# New_Schematic.net
KiCad netlist of a schematic drawn in EAGLE
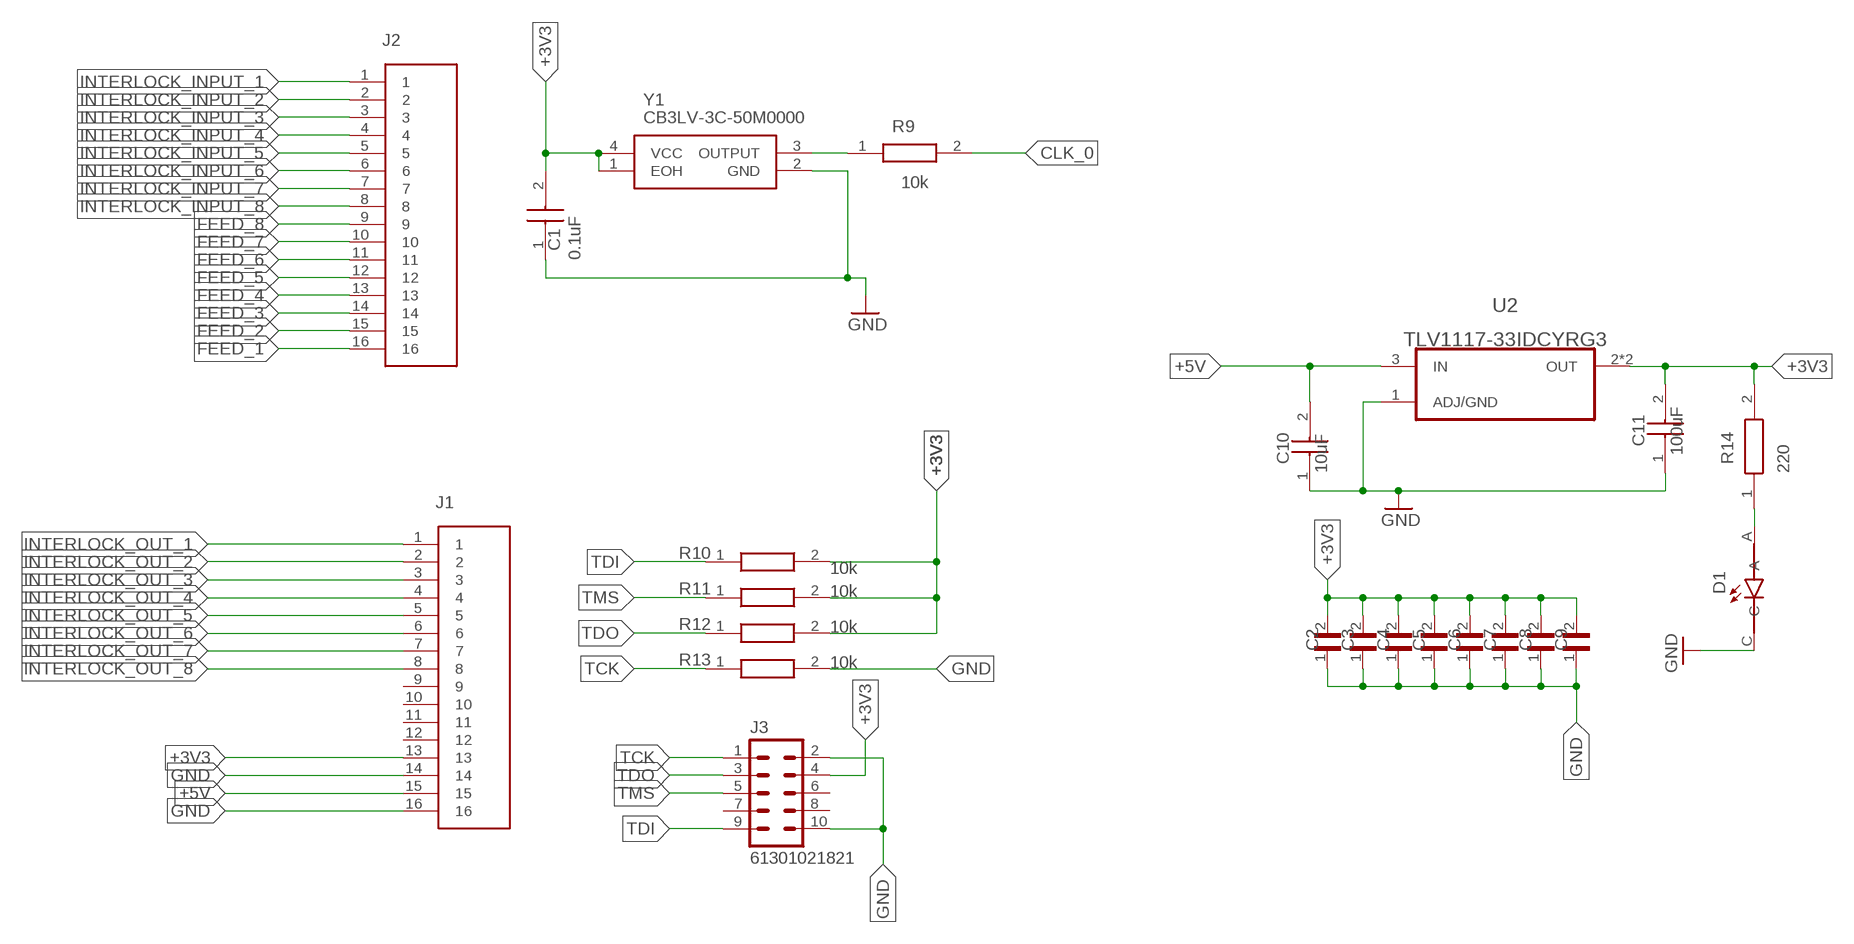
[diagram p0: schematic, sheet 1, part 1 of 2]
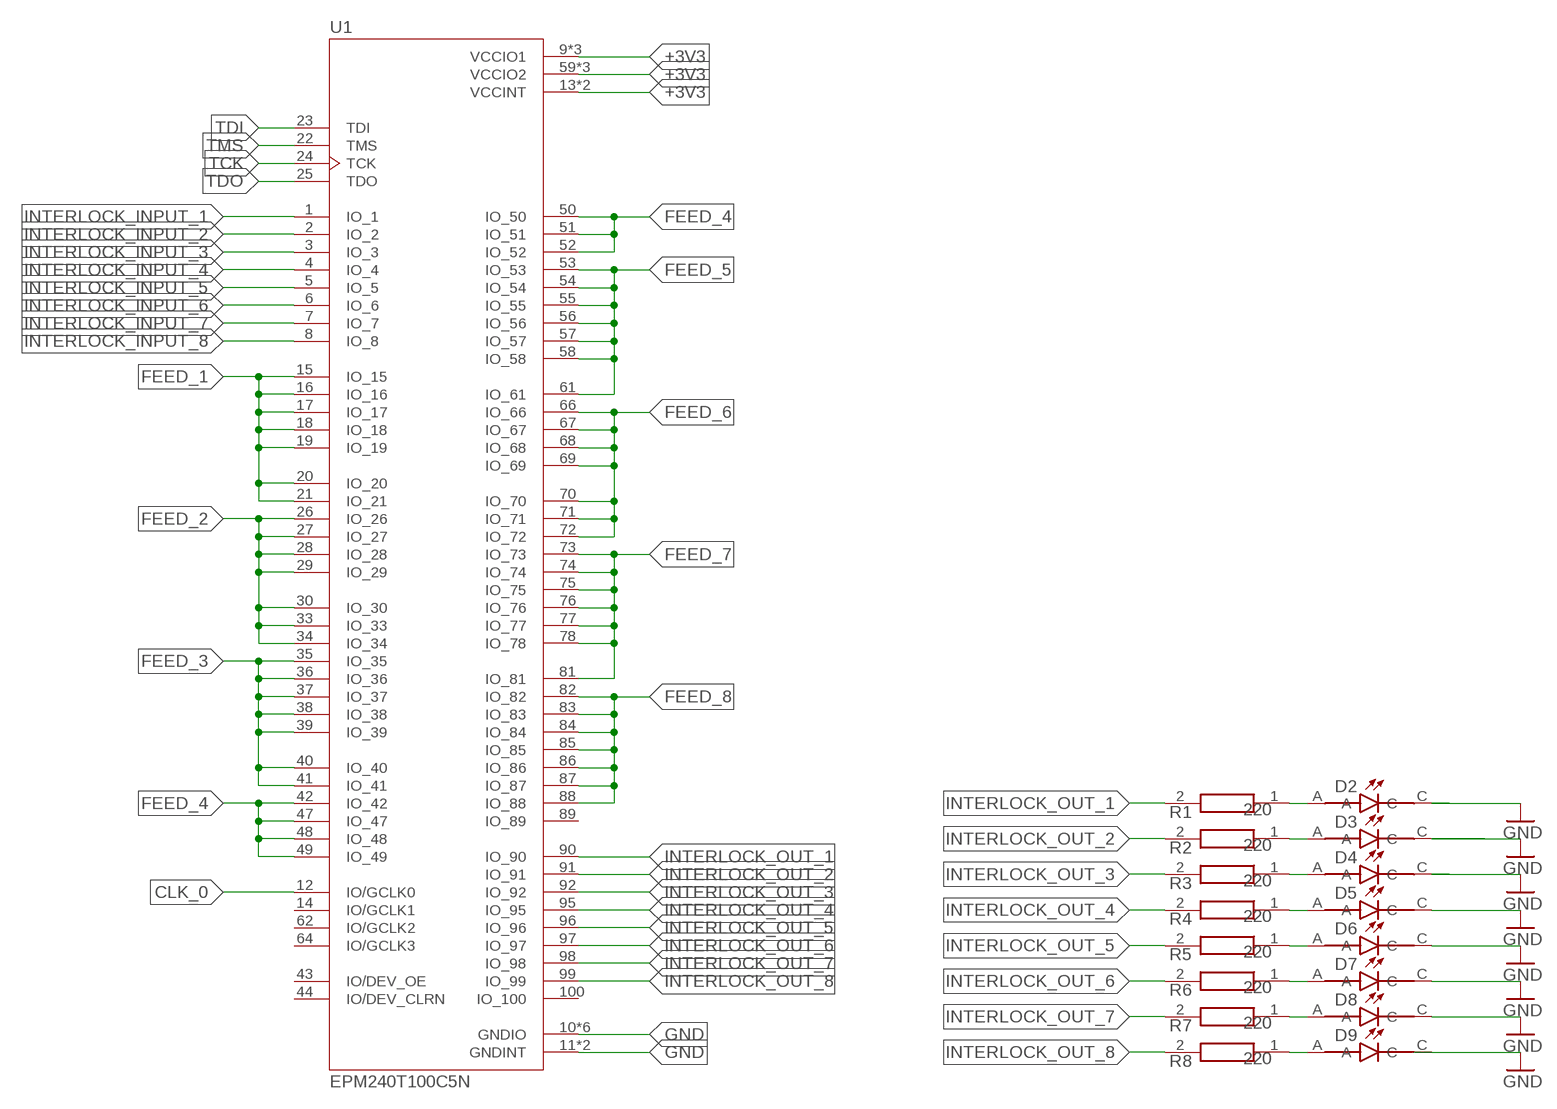
[diagram p1: schematic, sheet 1, part 2 of 2]

(export (version "E")
  (design (tool "Eeschema 10.0.6"))
  (components
    (comp (ref "C1")
      (value "GRM188R71C104MA01D")
      (footprint "eagle-import:CAPC1608X90N")
      (fields (field (name "MOUSER_PART_NUMBER") "81-GRM18R71C104MA01D") (field (name "C1") "0.1uF"))
      (libsource (lib "eagle-import") (part "GRM188R71C104MA01D"))
    )
    (comp (ref "C2")
      (value "GRM155R70J104KA01D")
      (footprint "eagle-import:CAPC1005X55N")
      (fields (field (name "DIGIKEY_PART_NUMBER") "490-6319-2-ND") (field (name "MF") "Murata"))
      (libsource (lib "eagle-import") (part "GRM155R70J104KA01D"))
    )
    (comp (ref "C3")
      (value "GRM155R70J104KA01D")
      (footprint "eagle-import:CAPC1005X55N")
      (fields (field (name "DIGIKEY_PART_NUMBER") "490-6319-2-ND") (field (name "MF") "Murata"))
      (libsource (lib "eagle-import") (part "GRM155R70J104KA01D"))
    )
    (comp (ref "C4")
      (value "GRM155R70J104KA01D")
      (footprint "eagle-import:CAPC1005X55N")
      (fields (field (name "DIGIKEY_PART_NUMBER") "490-6319-2-ND") (field (name "MF") "Murata"))
      (libsource (lib "eagle-import") (part "GRM155R70J104KA01D"))
    )
    (comp (ref "C5")
      (value "GRM155R70J104KA01D")
      (footprint "eagle-import:CAPC1005X55N")
      (fields (field (name "DIGIKEY_PART_NUMBER") "490-6319-2-ND") (field (name "MF") "Murata"))
      (libsource (lib "eagle-import") (part "GRM155R70J104KA01D"))
    )
    (comp (ref "C6")
      (value "GRM155R70J104KA01D")
      (footprint "eagle-import:CAPC1005X55N")
      (fields (field (name "DIGIKEY_PART_NUMBER") "490-6319-2-ND") (field (name "MF") "Murata"))
      (libsource (lib "eagle-import") (part "GRM155R70J104KA01D"))
    )
    (comp (ref "C7")
      (value "GRM155R70J104KA01D")
      (footprint "eagle-import:CAPC1005X55N")
      (fields (field (name "DIGIKEY_PART_NUMBER") "490-6319-2-ND") (field (name "MF") "Murata"))
      (libsource (lib "eagle-import") (part "GRM155R70J104KA01D"))
    )
    (comp (ref "C8")
      (value "GRM155R70J104KA01D")
      (footprint "eagle-import:CAPC1005X55N")
      (fields (field (name "DIGIKEY_PART_NUMBER") "490-6319-2-ND") (field (name "MF") "Murata"))
      (libsource (lib "eagle-import") (part "GRM155R70J104KA01D"))
    )
    (comp (ref "C9")
      (value "GRM155R70J104KA01D")
      (footprint "eagle-import:CAPC1005X55N")
      (fields (field (name "DIGIKEY_PART_NUMBER") "490-6319-2-ND") (field (name "MF") "Murata"))
      (libsource (lib "eagle-import") (part "GRM155R70J104KA01D"))
    )
    (comp (ref "C10")
      (value "0603X106M160CT")
      (footprint "eagle-import:CAPC1608X95N")
      (fields (field (name "C10") "10uF"))
      (libsource (lib "eagle-import") (part "0603X106M160CT"))
    )
    (comp (ref "C11")
      (value "0603X106M160CT")
      (footprint "eagle-import:CAPC1608X95N")
      (fields (field (name "C12") "100uF"))
      (libsource (lib "eagle-import") (part "0603X106M160CT"))
    )
    (comp (ref "D1")
      (value "HSMS-C190")
      (footprint "eagle-import:LEDM1608X80")
      (fields (field (name "MF") "Broadcom Limited"))
      (libsource (lib "eagle-import") (part "HSMS-C190"))
    )
    (comp (ref "D2")
      (value "HSMS-C190")
      (footprint "eagle-import:LEDM1608X80")
      (fields (field (name "MF") "Broadcom Limited"))
      (libsource (lib "eagle-import") (part "HSMS-C190"))
    )
    (comp (ref "D3")
      (value "HSMS-C190")
      (footprint "eagle-import:LEDM1608X80")
      (fields (field (name "MF") "Broadcom Limited"))
      (libsource (lib "eagle-import") (part "HSMS-C190"))
    )
    (comp (ref "D4")
      (value "HSMS-C190")
      (footprint "eagle-import:LEDM1608X80")
      (fields (field (name "MF") "Broadcom Limited"))
      (libsource (lib "eagle-import") (part "HSMS-C190"))
    )
    (comp (ref "D5")
      (value "HSMS-C190")
      (footprint "eagle-import:LEDM1608X80")
      (fields (field (name "MF") "Broadcom Limited"))
      (libsource (lib "eagle-import") (part "HSMS-C190"))
    )
    (comp (ref "D6")
      (value "HSMS-C190")
      (footprint "eagle-import:LEDM1608X80")
      (fields (field (name "MF") "Broadcom Limited"))
      (libsource (lib "eagle-import") (part "HSMS-C190"))
    )
    (comp (ref "D7")
      (value "HSMS-C190")
      (footprint "eagle-import:LEDM1608X80")
      (fields (field (name "MF") "Broadcom Limited"))
      (libsource (lib "eagle-import") (part "HSMS-C190"))
    )
    (comp (ref "D8")
      (value "HSMS-C190")
      (footprint "eagle-import:LEDM1608X80")
      (fields (field (name "MF") "Broadcom Limited"))
      (libsource (lib "eagle-import") (part "HSMS-C190"))
    )
    (comp (ref "D9")
      (value "HSMS-C190")
      (footprint "eagle-import:LEDM1608X80")
      (fields (field (name "MF") "Broadcom Limited"))
      (libsource (lib "eagle-import") (part "HSMS-C190"))
    )
    (comp (ref "J1")
      (value "1-2314812-6")
      (footprint "eagle-import:TE_1-2314812-6")
      (fields (field (name "DIGIKEY_PART_NUMBER") "17-1-2314812-6-ND") (field (name "MF") "TE Connectivity"))
      (libsource (lib "eagle-import") (part "1-2314812-6"))
    )
    (comp (ref "J2")
      (value "1-2314812-6")
      (footprint "eagle-import:TE_1-2314812-6")
      (fields (field (name "DIGIKEY_PART_NUMBER") "17-1-2314812-6-ND") (field (name "MF") "TE Connectivity"))
      (libsource (lib "eagle-import") (part "1-2314812-6"))
    )
    (comp (ref "J3")
      (value "61301021821")
      (footprint "eagle-import:2X05-PIN")
      (fields (field (name "MF") "Wurth Electronics"))
      (libsource (lib "eagle-import") (part "61301021821"))
    )
    (comp (ref "R1")
      (value "MCT06030D2200BP100")
      (footprint "eagle-import:RESC1608X55N")
      (fields (field (name "R14") "220"))
      (libsource (lib "eagle-import") (part "MCT06030D2200BP100"))
    )
    (comp (ref "R2")
      (value "MCT06030D2200BP100")
      (footprint "eagle-import:RESC1608X55N")
      (fields (field (name "R14") "220"))
      (libsource (lib "eagle-import") (part "MCT06030D2200BP100"))
    )
    (comp (ref "R3")
      (value "MCT06030D2200BP100")
      (footprint "eagle-import:RESC1608X55N")
      (fields (field (name "R14") "220"))
      (libsource (lib "eagle-import") (part "MCT06030D2200BP100"))
    )
    (comp (ref "R4")
      (value "MCT06030D2200BP100")
      (footprint "eagle-import:RESC1608X55N")
      (fields (field (name "R14") "220"))
      (libsource (lib "eagle-import") (part "MCT06030D2200BP100"))
    )
    (comp (ref "R5")
      (value "MCT06030D2200BP100")
      (footprint "eagle-import:RESC1608X55N")
      (fields (field (name "R14") "220"))
      (libsource (lib "eagle-import") (part "MCT06030D2200BP100"))
    )
    (comp (ref "R6")
      (value "MCT06030D2200BP100")
      (footprint "eagle-import:RESC1608X55N")
      (fields (field (name "R14") "220"))
      (libsource (lib "eagle-import") (part "MCT06030D2200BP100"))
    )
    (comp (ref "R7")
      (value "MCT06030D2200BP100")
      (footprint "eagle-import:RESC1608X55N")
      (fields (field (name "R14") "220"))
      (libsource (lib "eagle-import") (part "MCT06030D2200BP100"))
    )
    (comp (ref "R8")
      (value "MCT06030D2200BP100")
      (footprint "eagle-import:RESC1608X55N")
      (fields (field (name "R14") "220"))
      (libsource (lib "eagle-import") (part "MCT06030D2200BP100"))
    )
    (comp (ref "R9")
      (value "CRT0603-BY-1002EAS")
      (footprint "eagle-import:RESC1608X60N")
      (fields (field (name "MOUSER_PART_NUMBER") "652-CRT0603BY1002EAS") (field (name "R9") "10k"))
      (libsource (lib "eagle-import") (part "CRT0603-BY-1002EAS"))
    )
    (comp (ref "R10")
      (value "CRT0603-BY-1002EAS")
      (footprint "eagle-import:RESC1608X60N")
      (fields (field (name "MOUSER_PART_NUMBER") "652-CRT0603BY1002EAS") (field (name "R10") "10k"))
      (libsource (lib "eagle-import") (part "CRT0603-BY-1002EAS"))
    )
    (comp (ref "R11")
      (value "CRT0603-BY-1002EAS")
      (footprint "eagle-import:RESC1608X60N")
      (fields (field (name "MOUSER_PART_NUMBER") "652-CRT0603BY1002EAS") (field (name "R11") "10k"))
      (libsource (lib "eagle-import") (part "CRT0603-BY-1002EAS"))
    )
    (comp (ref "R12")
      (value "CRT0603-BY-1002EAS")
      (footprint "eagle-import:RESC1608X60N")
      (fields (field (name "MOUSER_PART_NUMBER") "652-CRT0603BY1002EAS") (field (name "R12") "10k"))
      (libsource (lib "eagle-import") (part "CRT0603-BY-1002EAS"))
    )
    (comp (ref "R13")
      (value "CRT0603-BY-1002EAS")
      (footprint "eagle-import:RESC1608X60N")
      (fields (field (name "MOUSER_PART_NUMBER") "652-CRT0603BY1002EAS") (field (name "R13") "10k"))
      (libsource (lib "eagle-import") (part "CRT0603-BY-1002EAS"))
    )
    (comp (ref "R14")
      (value "MCT06030D2200BP100")
      (footprint "eagle-import:RESC1608X55N")
      (fields (field (name "R14") "220"))
      (libsource (lib "eagle-import") (part "MCT06030D2200BP100"))
    )
    (comp (ref "U1")
      (value "EPM240T100C5N")
      (footprint "eagle-import:QFP50P1600X1600X120-100N")
      (fields (field (name "DIGIKEY_PART_NUMBER") "544-1964-ND") (field (name "MF") "Intel"))
      (libsource (lib "eagle-import") (part "EPM240T100C5N"))
    )
    (comp (ref "U2")
      (value "TLV1117-33IDCYRG3")
      (footprint "eagle-import:SOT230P700X180-4N")
      (fields (field (name "MF") "Texas Instruments"))
      (libsource (lib "eagle-import") (part "TLV1117-33IDCYRG3"))
    )
    (comp (ref "Y1")
      (value "CB3LV-3C-50M0000")
      (footprint "eagle-import:CB3LV3C50M0000")
      (fields (field (name "MOUSER_PART_NUMBER") "774-CB3LV-3C-50M0"))
      (libsource (lib "eagle-import") (part "CB3LV-3C-50M0000"))
    )
  )
  (nets
    (net (code "1") (name "+3V3") (class "Default")
      (node (ref "C1") (pin "2") (pinfunction "2_2") (pintype "bidirectional"))
      (node (ref "C11") (pin "2") (pinfunction "2_2") (pintype "bidirectional"))
      (node (ref "C2") (pin "2") (pinfunction "2_2") (pintype "passive"))
      (node (ref "C3") (pin "2") (pinfunction "2_2") (pintype "passive"))
      (node (ref "C4") (pin "2") (pinfunction "2_2") (pintype "passive"))
      (node (ref "C5") (pin "2") (pinfunction "2_2") (pintype "passive"))
      (node (ref "C6") (pin "2") (pinfunction "2_2") (pintype "passive"))
      (node (ref "C7") (pin "2") (pinfunction "2_2") (pintype "passive"))
      (node (ref "C8") (pin "2") (pinfunction "2_2") (pintype "passive"))
      (node (ref "C9") (pin "2") (pinfunction "2_2") (pintype "passive"))
      (node (ref "J1") (pin "13") (pinfunction "13_13") (pintype "passive"))
      (node (ref "J3") (pin "4") (pinfunction "4_4") (pintype "passive"))
      (node (ref "R10") (pin "2") (pinfunction "2_2") (pintype "bidirectional"))
      (node (ref "R11") (pin "2") (pinfunction "2_2") (pintype "bidirectional"))
      (node (ref "R12") (pin "2") (pinfunction "2_2") (pintype "bidirectional"))
      (node (ref "R14") (pin "2") (pinfunction "2_2") (pintype "bidirectional"))
      (node (ref "U1") (pin "13") (pinfunction "VCCINT_13") (pintype "power_in"))
      (node (ref "U1") (pin "31") (pinfunction "VCCIO1_31") (pintype "power_in"))
      (node (ref "U1") (pin "45") (pinfunction "VCCIO1_45") (pintype "power_in"))
      (node (ref "U1") (pin "59") (pinfunction "VCCIO2_59") (pintype "power_in"))
      (node (ref "U1") (pin "63") (pinfunction "VCCINT_63") (pintype "power_in"))
      (node (ref "U1") (pin "80") (pinfunction "VCCIO2_80") (pintype "power_in"))
      (node (ref "U1") (pin "9") (pinfunction "VCCIO1_9") (pintype "power_in"))
      (node (ref "U1") (pin "94") (pinfunction "VCCIO2_94") (pintype "power_in"))
      (node (ref "U2") (pin "2") (pinfunction "OUT_2") (pintype "output"))
      (node (ref "U2") (pin "4") (pinfunction "OUT_4") (pintype "output"))
      (node (ref "Y1") (pin "1") (pinfunction "EOH_1") (pintype "bidirectional"))
      (node (ref "Y1") (pin "4") (pinfunction "VCC_4") (pintype "bidirectional"))
    )
    (net (code "2") (name "+5V") (class "Default")
      (node (ref "C10") (pin "2") (pinfunction "2_2") (pintype "bidirectional"))
      (node (ref "J1") (pin "15") (pinfunction "15_15") (pintype "passive"))
      (node (ref "U2") (pin "3") (pinfunction "IN_3") (pintype "input"))
    )
    (net (code "3") (name "CLK_0") (class "Default")
      (node (ref "R9") (pin "2") (pinfunction "2_2") (pintype "bidirectional"))
      (node (ref "U1") (pin "12") (pinfunction "IO/GCLK0_12") (pintype "bidirectional"))
    )
    (net (code "4") (name "FEED_1") (class "Default")
      (node (ref "J2") (pin "16") (pinfunction "16_16") (pintype "passive"))
      (node (ref "U1") (pin "15") (pinfunction "IO_15_15") (pintype "bidirectional"))
      (node (ref "U1") (pin "16") (pinfunction "IO_16_16") (pintype "bidirectional"))
      (node (ref "U1") (pin "17") (pinfunction "IO_17_17") (pintype "bidirectional"))
      (node (ref "U1") (pin "18") (pinfunction "IO_18_18") (pintype "bidirectional"))
      (node (ref "U1") (pin "19") (pinfunction "IO_19_19") (pintype "bidirectional"))
      (node (ref "U1") (pin "20") (pinfunction "IO_20_20") (pintype "bidirectional"))
      (node (ref "U1") (pin "21") (pinfunction "IO_21_21") (pintype "bidirectional"))
    )
    (net (code "5") (name "FEED_2") (class "Default")
      (node (ref "J2") (pin "15") (pinfunction "15_15") (pintype "passive"))
      (node (ref "U1") (pin "26") (pinfunction "IO_26_26") (pintype "bidirectional"))
      (node (ref "U1") (pin "27") (pinfunction "IO_27_27") (pintype "bidirectional"))
      (node (ref "U1") (pin "28") (pinfunction "IO_28_28") (pintype "bidirectional"))
      (node (ref "U1") (pin "29") (pinfunction "IO_29_29") (pintype "bidirectional"))
      (node (ref "U1") (pin "30") (pinfunction "IO_30_30") (pintype "bidirectional"))
      (node (ref "U1") (pin "33") (pinfunction "IO_33_33") (pintype "bidirectional"))
      (node (ref "U1") (pin "34") (pinfunction "IO_34_34") (pintype "bidirectional"))
    )
    (net (code "6") (name "FEED_3") (class "Default")
      (node (ref "J2") (pin "14") (pinfunction "14_14") (pintype "passive"))
      (node (ref "U1") (pin "35") (pinfunction "IO_35_35") (pintype "bidirectional"))
      (node (ref "U1") (pin "36") (pinfunction "IO_36_36") (pintype "bidirectional"))
      (node (ref "U1") (pin "37") (pinfunction "IO_37_37") (pintype "bidirectional"))
      (node (ref "U1") (pin "38") (pinfunction "IO_38_38") (pintype "bidirectional"))
      (node (ref "U1") (pin "39") (pinfunction "IO_39_39") (pintype "bidirectional"))
      (node (ref "U1") (pin "40") (pinfunction "IO_40_40") (pintype "bidirectional"))
      (node (ref "U1") (pin "41") (pinfunction "IO_41_41") (pintype "bidirectional"))
    )
    (net (code "7") (name "FEED_4") (class "Default")
      (node (ref "J2") (pin "13") (pinfunction "13_13") (pintype "passive"))
      (node (ref "U1") (pin "42") (pinfunction "IO_42_42") (pintype "bidirectional"))
      (node (ref "U1") (pin "47") (pinfunction "IO_47_47") (pintype "bidirectional"))
      (node (ref "U1") (pin "48") (pinfunction "IO_48_48") (pintype "bidirectional"))
      (node (ref "U1") (pin "49") (pinfunction "IO_49_49") (pintype "bidirectional"))
      (node (ref "U1") (pin "50") (pinfunction "IO_50_50") (pintype "bidirectional"))
      (node (ref "U1") (pin "51") (pinfunction "IO_51_51") (pintype "bidirectional"))
      (node (ref "U1") (pin "52") (pinfunction "IO_52_52") (pintype "bidirectional"))
    )
    (net (code "8") (name "FEED_5") (class "Default")
      (node (ref "J2") (pin "12") (pinfunction "12_12") (pintype "passive"))
      (node (ref "U1") (pin "53") (pinfunction "IO_53_53") (pintype "bidirectional"))
      (node (ref "U1") (pin "54") (pinfunction "IO_54_54") (pintype "bidirectional"))
      (node (ref "U1") (pin "55") (pinfunction "IO_55_55") (pintype "bidirectional"))
      (node (ref "U1") (pin "56") (pinfunction "IO_56_56") (pintype "bidirectional"))
      (node (ref "U1") (pin "57") (pinfunction "IO_57_57") (pintype "bidirectional"))
      (node (ref "U1") (pin "58") (pinfunction "IO_58_58") (pintype "bidirectional"))
      (node (ref "U1") (pin "61") (pinfunction "IO_61_61") (pintype "bidirectional"))
    )
    (net (code "9") (name "FEED_6") (class "Default")
      (node (ref "J2") (pin "11") (pinfunction "11_11") (pintype "passive"))
      (node (ref "U1") (pin "66") (pinfunction "IO_66_66") (pintype "bidirectional"))
      (node (ref "U1") (pin "67") (pinfunction "IO_67_67") (pintype "bidirectional"))
      (node (ref "U1") (pin "68") (pinfunction "IO_68_68") (pintype "bidirectional"))
      (node (ref "U1") (pin "69") (pinfunction "IO_69_69") (pintype "bidirectional"))
      (node (ref "U1") (pin "70") (pinfunction "IO_70_70") (pintype "bidirectional"))
      (node (ref "U1") (pin "71") (pinfunction "IO_71_71") (pintype "bidirectional"))
      (node (ref "U1") (pin "72") (pinfunction "IO_72_72") (pintype "bidirectional"))
    )
    (net (code "10") (name "FEED_7") (class "Default")
      (node (ref "J2") (pin "10") (pinfunction "10_10") (pintype "passive"))
      (node (ref "U1") (pin "73") (pinfunction "IO_73_73") (pintype "bidirectional"))
      (node (ref "U1") (pin "74") (pinfunction "IO_74_74") (pintype "bidirectional"))
      (node (ref "U1") (pin "75") (pinfunction "IO_75_75") (pintype "bidirectional"))
      (node (ref "U1") (pin "76") (pinfunction "IO_76_76") (pintype "bidirectional"))
      (node (ref "U1") (pin "77") (pinfunction "IO_77_77") (pintype "bidirectional"))
      (node (ref "U1") (pin "78") (pinfunction "IO_78_78") (pintype "bidirectional"))
      (node (ref "U1") (pin "81") (pinfunction "IO_81_81") (pintype "bidirectional"))
    )
    (net (code "11") (name "FEED_8") (class "Default")
      (node (ref "J2") (pin "9") (pinfunction "9_9") (pintype "passive"))
      (node (ref "U1") (pin "82") (pinfunction "IO_82_82") (pintype "bidirectional"))
      (node (ref "U1") (pin "83") (pinfunction "IO_83_83") (pintype "bidirectional"))
      (node (ref "U1") (pin "84") (pinfunction "IO_84_84") (pintype "bidirectional"))
      (node (ref "U1") (pin "85") (pinfunction "IO_85_85") (pintype "bidirectional"))
      (node (ref "U1") (pin "86") (pinfunction "IO_86_86") (pintype "bidirectional"))
      (node (ref "U1") (pin "87") (pinfunction "IO_87_87") (pintype "bidirectional"))
      (node (ref "U1") (pin "88") (pinfunction "IO_88_88") (pintype "bidirectional"))
    )
    (net (code "12") (name "GND") (class "Default")
      (node (ref "C1") (pin "1") (pinfunction "1_1") (pintype "bidirectional"))
      (node (ref "C10") (pin "1") (pinfunction "1_1") (pintype "bidirectional"))
      (node (ref "C11") (pin "1") (pinfunction "1_1") (pintype "bidirectional"))
      (node (ref "C2") (pin "1") (pinfunction "1_1") (pintype "passive"))
      (node (ref "C3") (pin "1") (pinfunction "1_1") (pintype "passive"))
      (node (ref "C4") (pin "1") (pinfunction "1_1") (pintype "passive"))
      (node (ref "C5") (pin "1") (pinfunction "1_1") (pintype "passive"))
      (node (ref "C6") (pin "1") (pinfunction "1_1") (pintype "passive"))
      (node (ref "C7") (pin "1") (pinfunction "1_1") (pintype "passive"))
      (node (ref "C8") (pin "1") (pinfunction "1_1") (pintype "passive"))
      (node (ref "C9") (pin "1") (pinfunction "1_1") (pintype "passive"))
      (node (ref "D1") (pin "C") (pinfunction "C_C") (pintype "passive"))
      (node (ref "D2") (pin "C") (pinfunction "C_C") (pintype "passive"))
      (node (ref "D3") (pin "C") (pinfunction "C_C") (pintype "passive"))
      (node (ref "D4") (pin "C") (pinfunction "C_C") (pintype "passive"))
      (node (ref "D5") (pin "C") (pinfunction "C_C") (pintype "passive"))
      (node (ref "D6") (pin "C") (pinfunction "C_C") (pintype "passive"))
      (node (ref "D7") (pin "C") (pinfunction "C_C") (pintype "passive"))
      (node (ref "D8") (pin "C") (pinfunction "C_C") (pintype "passive"))
      (node (ref "D9") (pin "C") (pinfunction "C_C") (pintype "passive"))
      (node (ref "J1") (pin "14") (pinfunction "14_14") (pintype "passive"))
      (node (ref "J1") (pin "16") (pinfunction "16_16") (pintype "passive"))
      (node (ref "J3") (pin "10") (pinfunction "10_10") (pintype "passive"))
      (node (ref "J3") (pin "2") (pinfunction "2_2") (pintype "passive"))
      (node (ref "R13") (pin "2") (pinfunction "2_2") (pintype "bidirectional"))
      (node (ref "U1") (pin "10") (pinfunction "GNDIO_10") (pintype "power_in"))
      (node (ref "U1") (pin "11") (pinfunction "GNDINT_11") (pintype "power_in"))
      (node (ref "U1") (pin "32") (pinfunction "GNDIO_32") (pintype "power_in"))
      (node (ref "U1") (pin "46") (pinfunction "GNDIO_46") (pintype "power_in"))
      (node (ref "U1") (pin "60") (pinfunction "GNDIO_60") (pintype "power_in"))
      (node (ref "U1") (pin "65") (pinfunction "GNDINT_65") (pintype "power_in"))
      (node (ref "U1") (pin "79") (pinfunction "GNDIO_79") (pintype "power_in"))
      (node (ref "U1") (pin "93") (pinfunction "GNDIO_93") (pintype "power_in"))
      (node (ref "U2") (pin "1") (pinfunction "ADJ/GND_1") (pintype "bidirectional"))
      (node (ref "Y1") (pin "2") (pinfunction "GND_2") (pintype "bidirectional"))
    )
    (net (code "13") (name "INTERLOCK_INPUT_1") (class "Default")
      (node (ref "J2") (pin "1") (pinfunction "1_1") (pintype "passive"))
      (node (ref "U1") (pin "1") (pinfunction "IO_1_1") (pintype "bidirectional"))
    )
    (net (code "14") (name "INTERLOCK_INPUT_2") (class "Default")
      (node (ref "J2") (pin "2") (pinfunction "2_2") (pintype "passive"))
      (node (ref "U1") (pin "2") (pinfunction "IO_2_2") (pintype "bidirectional"))
    )
    (net (code "15") (name "INTERLOCK_INPUT_3") (class "Default")
      (node (ref "J2") (pin "3") (pinfunction "3_3") (pintype "passive"))
      (node (ref "U1") (pin "3") (pinfunction "IO_3_3") (pintype "bidirectional"))
    )
    (net (code "16") (name "INTERLOCK_INPUT_4") (class "Default")
      (node (ref "J2") (pin "4") (pinfunction "4_4") (pintype "passive"))
      (node (ref "U1") (pin "4") (pinfunction "IO_4_4") (pintype "bidirectional"))
    )
    (net (code "17") (name "INTERLOCK_INPUT_5") (class "Default")
      (node (ref "J2") (pin "5") (pinfunction "5_5") (pintype "passive"))
      (node (ref "U1") (pin "5") (pinfunction "IO_5_5") (pintype "bidirectional"))
    )
    (net (code "18") (name "INTERLOCK_INPUT_6") (class "Default")
      (node (ref "J2") (pin "6") (pinfunction "6_6") (pintype "passive"))
      (node (ref "U1") (pin "6") (pinfunction "IO_6_6") (pintype "bidirectional"))
    )
    (net (code "19") (name "INTERLOCK_INPUT_7") (class "Default")
      (node (ref "J2") (pin "7") (pinfunction "7_7") (pintype "passive"))
      (node (ref "U1") (pin "7") (pinfunction "IO_7_7") (pintype "bidirectional"))
    )
    (net (code "20") (name "INTERLOCK_INPUT_8") (class "Default")
      (node (ref "J2") (pin "8") (pinfunction "8_8") (pintype "passive"))
      (node (ref "U1") (pin "8") (pinfunction "IO_8_8") (pintype "bidirectional"))
    )
    (net (code "21") (name "INTERLOCK_OUT_1") (class "Default")
      (node (ref "J1") (pin "1") (pinfunction "1_1") (pintype "passive"))
      (node (ref "R1") (pin "2") (pinfunction "2_2") (pintype "bidirectional"))
      (node (ref "U1") (pin "90") (pinfunction "IO_90_90") (pintype "bidirectional"))
    )
    (net (code "22") (name "INTERLOCK_OUT_2") (class "Default")
      (node (ref "J1") (pin "2") (pinfunction "2_2") (pintype "passive"))
      (node (ref "R2") (pin "2") (pinfunction "2_2") (pintype "bidirectional"))
      (node (ref "U1") (pin "91") (pinfunction "IO_91_91") (pintype "bidirectional"))
    )
    (net (code "23") (name "INTERLOCK_OUT_3") (class "Default")
      (node (ref "J1") (pin "3") (pinfunction "3_3") (pintype "passive"))
      (node (ref "R3") (pin "2") (pinfunction "2_2") (pintype "bidirectional"))
      (node (ref "U1") (pin "92") (pinfunction "IO_92_92") (pintype "bidirectional"))
    )
    (net (code "24") (name "INTERLOCK_OUT_4") (class "Default")
      (node (ref "J1") (pin "4") (pinfunction "4_4") (pintype "passive"))
      (node (ref "R4") (pin "2") (pinfunction "2_2") (pintype "bidirectional"))
      (node (ref "U1") (pin "95") (pinfunction "IO_95_95") (pintype "bidirectional"))
    )
    (net (code "25") (name "INTERLOCK_OUT_5") (class "Default")
      (node (ref "J1") (pin "5") (pinfunction "5_5") (pintype "passive"))
      (node (ref "R5") (pin "2") (pinfunction "2_2") (pintype "bidirectional"))
      (node (ref "U1") (pin "96") (pinfunction "IO_96_96") (pintype "bidirectional"))
    )
    (net (code "26") (name "INTERLOCK_OUT_6") (class "Default")
      (node (ref "J1") (pin "6") (pinfunction "6_6") (pintype "passive"))
      (node (ref "R6") (pin "2") (pinfunction "2_2") (pintype "bidirectional"))
      (node (ref "U1") (pin "97") (pinfunction "IO_97_97") (pintype "bidirectional"))
    )
    (net (code "27") (name "INTERLOCK_OUT_7") (class "Default")
      (node (ref "J1") (pin "7") (pinfunction "7_7") (pintype "passive"))
      (node (ref "R7") (pin "2") (pinfunction "2_2") (pintype "bidirectional"))
      (node (ref "U1") (pin "98") (pinfunction "IO_98_98") (pintype "bidirectional"))
    )
    (net (code "28") (name "INTERLOCK_OUT_8") (class "Default")
      (node (ref "J1") (pin "8") (pinfunction "8_8") (pintype "passive"))
      (node (ref "R8") (pin "2") (pinfunction "2_2") (pintype "bidirectional"))
      (node (ref "U1") (pin "99") (pinfunction "IO_99_99") (pintype "bidirectional"))
    )
    (net (code "29") (name "Net-(D1-PadA)") (class "Default")
      (node (ref "D1") (pin "A") (pinfunction "A_A") (pintype "passive"))
      (node (ref "R14") (pin "1") (pinfunction "1_1") (pintype "bidirectional"))
    )
    (net (code "30") (name "Net-(D2-PadA)") (class "Default")
      (node (ref "D2") (pin "A") (pinfunction "A_A") (pintype "passive"))
      (node (ref "R1") (pin "1") (pinfunction "1_1") (pintype "bidirectional"))
    )
    (net (code "31") (name "Net-(D3-PadA)") (class "Default")
      (node (ref "D3") (pin "A") (pinfunction "A_A") (pintype "passive"))
      (node (ref "R2") (pin "1") (pinfunction "1_1") (pintype "bidirectional"))
    )
    (net (code "32") (name "Net-(D4-PadA)") (class "Default")
      (node (ref "D4") (pin "A") (pinfunction "A_A") (pintype "passive"))
      (node (ref "R3") (pin "1") (pinfunction "1_1") (pintype "bidirectional"))
    )
    (net (code "33") (name "Net-(D5-PadA)") (class "Default")
      (node (ref "D5") (pin "A") (pinfunction "A_A") (pintype "passive"))
      (node (ref "R4") (pin "1") (pinfunction "1_1") (pintype "bidirectional"))
    )
    (net (code "34") (name "Net-(D6-PadA)") (class "Default")
      (node (ref "D6") (pin "A") (pinfunction "A_A") (pintype "passive"))
      (node (ref "R5") (pin "1") (pinfunction "1_1") (pintype "bidirectional"))
    )
    (net (code "35") (name "Net-(D7-PadA)") (class "Default")
      (node (ref "D7") (pin "A") (pinfunction "A_A") (pintype "passive"))
      (node (ref "R6") (pin "1") (pinfunction "1_1") (pintype "bidirectional"))
    )
    (net (code "36") (name "Net-(D8-PadA)") (class "Default")
      (node (ref "D8") (pin "A") (pinfunction "A_A") (pintype "passive"))
      (node (ref "R7") (pin "1") (pinfunction "1_1") (pintype "bidirectional"))
    )
    (net (code "37") (name "Net-(D9-PadA)") (class "Default")
      (node (ref "D9") (pin "A") (pinfunction "A_A") (pintype "passive"))
      (node (ref "R8") (pin "1") (pinfunction "1_1") (pintype "bidirectional"))
    )
    (net (code "38") (name "Net-(Y1-OUTPUT)") (class "Default")
      (node (ref "R9") (pin "1") (pinfunction "1_1") (pintype "bidirectional"))
      (node (ref "Y1") (pin "3") (pinfunction "OUTPUT_3") (pintype "bidirectional"))
    )
    (net (code "39") (name "TCK") (class "Default")
      (node (ref "J3") (pin "1") (pinfunction "1_1") (pintype "passive"))
      (node (ref "R13") (pin "1") (pinfunction "1_1") (pintype "bidirectional"))
      (node (ref "U1") (pin "24") (pinfunction "TCK_24") (pintype "input"))
    )
    (net (code "40") (name "TDI") (class "Default")
      (node (ref "J3") (pin "9") (pinfunction "9_9") (pintype "passive"))
      (node (ref "R10") (pin "1") (pinfunction "1_1") (pintype "bidirectional"))
      (node (ref "U1") (pin "23") (pinfunction "TDI_23") (pintype "input"))
    )
    (net (code "41") (name "TDO") (class "Default")
      (node (ref "J3") (pin "3") (pinfunction "3_3") (pintype "passive"))
      (node (ref "R12") (pin "1") (pinfunction "1_1") (pintype "bidirectional"))
      (node (ref "U1") (pin "25") (pinfunction "TDO_25") (pintype "output"))
    )
    (net (code "42") (name "TMS") (class "Default")
      (node (ref "J3") (pin "5") (pinfunction "5_5") (pintype "passive"))
      (node (ref "R11") (pin "1") (pinfunction "1_1") (pintype "bidirectional"))
      (node (ref "U1") (pin "22") (pinfunction "TMS_22") (pintype "input"))
    )
    (net (code "43") (name "unconnected-(J1-Pad9)") (class "Default")
      (node (ref "J1") (pin "9") (pinfunction "9_9") (pintype "passive"))
    )
    (net (code "44") (name "unconnected-(J1-Pad10)") (class "Default")
      (node (ref "J1") (pin "10") (pinfunction "10_10") (pintype "passive"))
    )
    (net (code "45") (name "unconnected-(J1-Pad11)") (class "Default")
      (node (ref "J1") (pin "11") (pinfunction "11_11") (pintype "passive"))
    )
    (net (code "46") (name "unconnected-(J1-Pad12)") (class "Default")
      (node (ref "J1") (pin "12") (pinfunction "12_12") (pintype "passive"))
    )
    (net (code "47") (name "unconnected-(J3-Pad6)") (class "Default")
      (node (ref "J3") (pin "6") (pinfunction "6_6") (pintype "passive"))
    )
    (net (code "48") (name "unconnected-(J3-Pad7)") (class "Default")
      (node (ref "J3") (pin "7") (pinfunction "7_7") (pintype "passive"))
    )
    (net (code "49") (name "unconnected-(J3-Pad8)") (class "Default")
      (node (ref "J3") (pin "8") (pinfunction "8_8") (pintype "passive"))
    )
    (net (code "50") (name "unconnected-(U1-IO_89-Pad89)") (class "Default")
      (node (ref "U1") (pin "89") (pinfunction "IO_89_89") (pintype "bidirectional"))
    )
    (net (code "51") (name "unconnected-(U1-IO_100-Pad100)") (class "Default")
      (node (ref "U1") (pin "100") (pinfunction "IO_100_100") (pintype "bidirectional"))
    )
    (net (code "52") (name "unconnected-(U1-IO{slash}DEV_CLRN-Pad44)") (class "Default")
      (node (ref "U1") (pin "44") (pinfunction "IO/DEV_CLRN_44") (pintype "bidirectional"))
    )
    (net (code "53") (name "unconnected-(U1-IO{slash}DEV_OE-Pad43)") (class "Default")
      (node (ref "U1") (pin "43") (pinfunction "IO/DEV_OE_43") (pintype "bidirectional"))
    )
    (net (code "54") (name "unconnected-(U1-IO{slash}GCLK1-Pad14)") (class "Default")
      (node (ref "U1") (pin "14") (pinfunction "IO/GCLK1_14") (pintype "bidirectional"))
    )
    (net (code "55") (name "unconnected-(U1-IO{slash}GCLK2-Pad62)") (class "Default")
      (node (ref "U1") (pin "62") (pinfunction "IO/GCLK2_62") (pintype "bidirectional"))
    )
    (net (code "56") (name "unconnected-(U1-IO{slash}GCLK3-Pad64)") (class "Default")
      (node (ref "U1") (pin "64") (pinfunction "IO/GCLK3_64") (pintype "bidirectional"))
    )
  )
)
